# oc75_v5.net
KiCad netlist of a schematic drawn in EAGLE
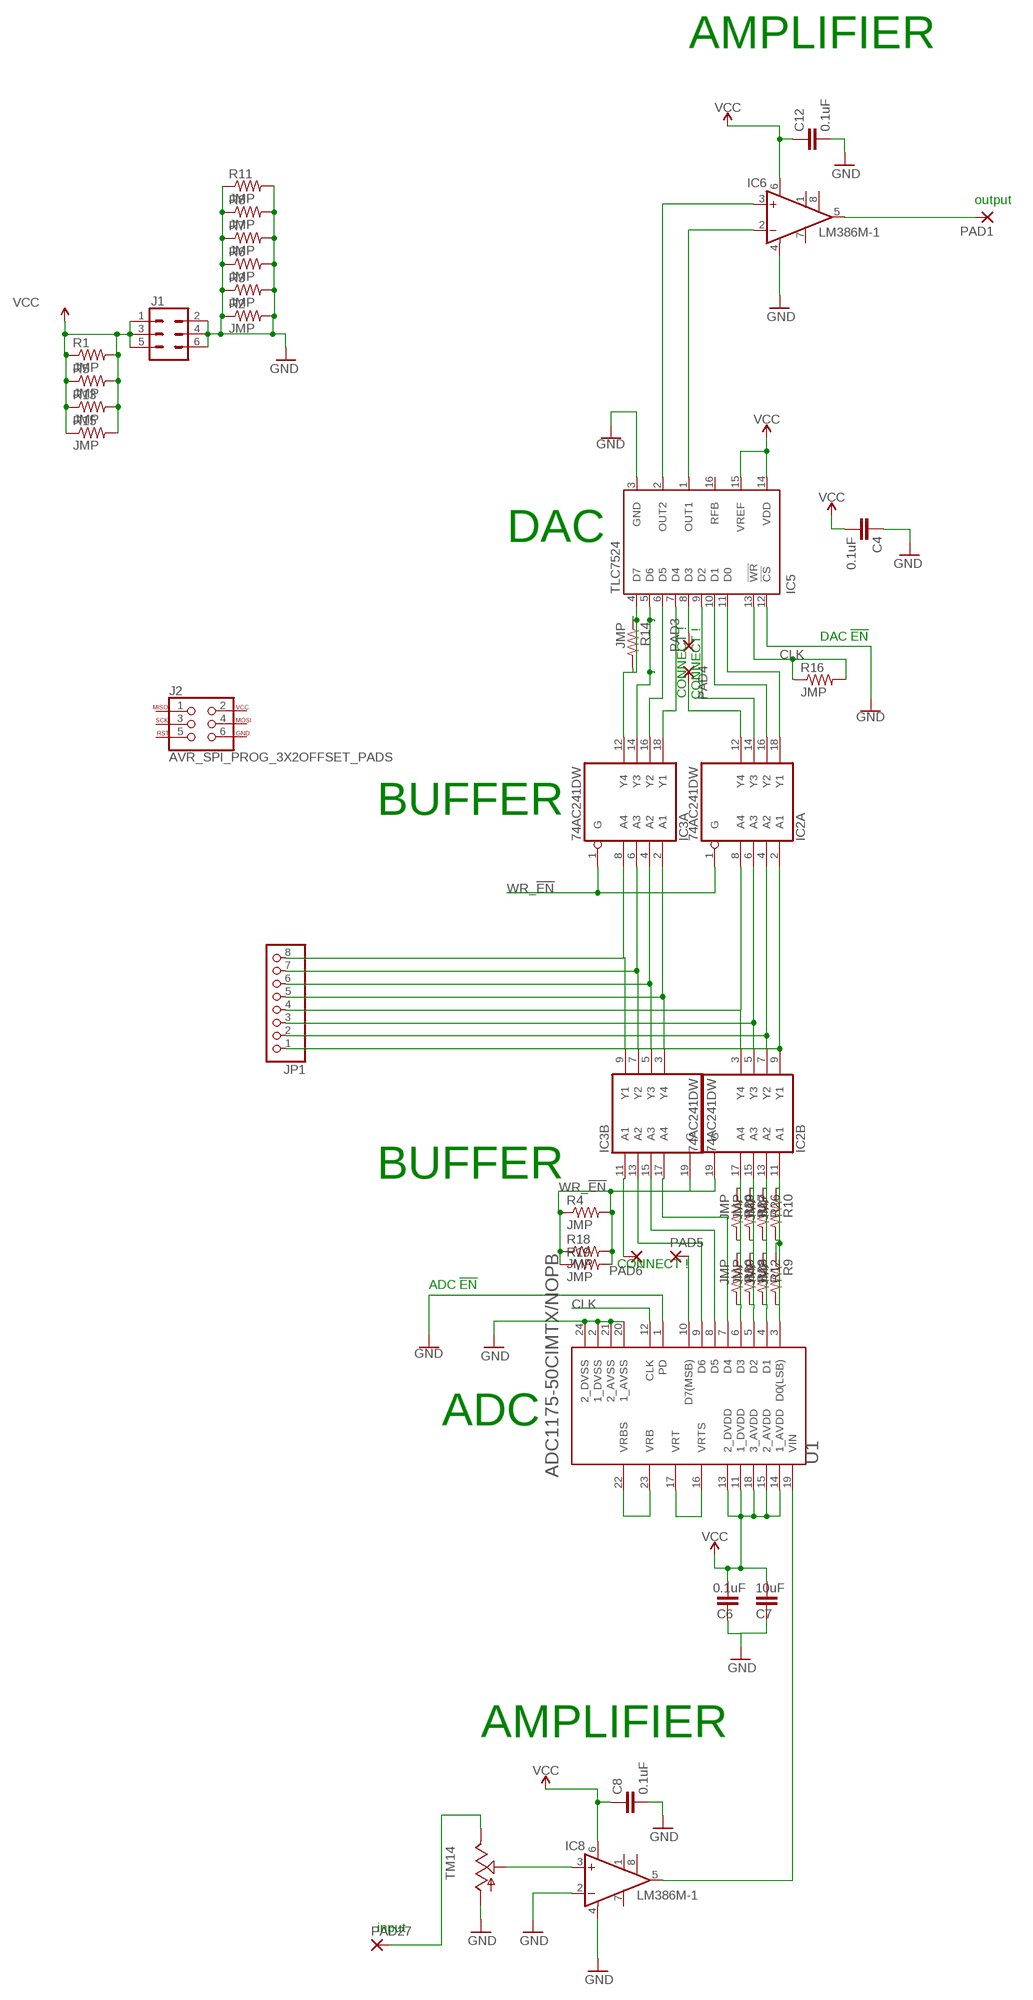
[diagram p0: schematic, sheet 1]

(export (version "E")
  (design (tool "Eeschema 10.0.6"))
  (components
    (comp (ref "C4")
      (value "0.1uF")
      (footprint "eagle-import:1206")
      (libsource (lib "eagle-import") (part "1.0UF-1206-50V-10%"))
    )
    (comp (ref "C6")
      (value "0.1uF")
      (footprint "eagle-import:1206")
      (libsource (lib "eagle-import") (part "1.0UF-1206-50V-10%"))
    )
    (comp (ref "C7")
      (value "10uF")
      (footprint "eagle-import:1206")
      (libsource (lib "eagle-import") (part "1.0UF-1206-50V-10%"))
    )
    (comp (ref "C8")
      (value "0.1uF")
      (footprint "eagle-import:1206")
      (libsource (lib "eagle-import") (part "1.0UF-1206-50V-10%"))
    )
    (comp (ref "C12")
      (value "0.1uF")
      (footprint "eagle-import:1206")
      (libsource (lib "eagle-import") (part "1.0UF-1206-50V-10%"))
    )
    (comp (ref "IC2")
      (value "74AC241DW")
      (footprint "eagle-import:SO20W")
      (libsource (lib "eagle-import") (part "74241DWAC"))
    )
    (comp (ref "IC3")
      (value "74AC241DW")
      (footprint "eagle-import:SO20W")
      (libsource (lib "eagle-import") (part "74241DWAC"))
    )
    (comp (ref "IC5")
      (value "TLC7524")
      (footprint "eagle-import:SO16")
      (libsource (lib "eagle-import") (part "TLC7524"))
    )
    (comp (ref "IC6")
      (value "LM386M-1")
      (footprint "eagle-import:SO08")
      (libsource (lib "eagle-import") (part "LM386?-M1"))
    )
    (comp (ref "IC8")
      (value "LM386M-1")
      (footprint "eagle-import:SO08")
      (libsource (lib "eagle-import") (part "LM386?-M1"))
    )
    (comp (ref "J1")
      (value "CONN_03X2FEMALE_SMD")
      (footprint "eagle-import:2X3_SMD")
      (libsource (lib "eagle-import") (part "CONN_03X2FEMALE_SMD"))
    )
    (comp (ref "J2")
      (value "AVR_SPI_PROG_3X2OFFSET_PADS")
      (footprint "eagle-import:2X3_OFFSET")
      (libsource (lib "eagle-import") (part "AVR_SPI_PROG_3X2OFFSET_PADS"))
    )
    (comp (ref "JP1")
      (value "PINHD-1X8BIG")
      (footprint "eagle-import:1X08-BIG")
      (libsource (lib "eagle-import") (part "PINHD-1X8BIG"))
    )
    (comp (ref "PAD1")
      (value "SMD2")
      (footprint "eagle-import:SMD1,27-2,54")
      (libsource (lib "eagle-import") (part "SMD2"))
    )
    (comp (ref "PAD3")
      (value "SMD2")
      (footprint "eagle-import:SMD1,27-2,54")
      (libsource (lib "eagle-import") (part "SMD2"))
    )
    (comp (ref "PAD4")
      (value "SMD2")
      (footprint "eagle-import:SMD1,27-2,54")
      (libsource (lib "eagle-import") (part "SMD2"))
    )
    (comp (ref "PAD5")
      (value "SMD2")
      (footprint "eagle-import:SMD1,27-2,54")
      (libsource (lib "eagle-import") (part "SMD2"))
    )
    (comp (ref "PAD6")
      (value "SMD2")
      (footprint "eagle-import:SMD1,27-2,54")
      (libsource (lib "eagle-import") (part "SMD2"))
    )
    (comp (ref "PAD27")
      (value "SMD2")
      (footprint "eagle-import:SMD1,27-2,54")
      (libsource (lib "eagle-import") (part "SMD2"))
    )
    (comp (ref "R1")
      (value "JMP")
      (footprint "eagle-import:M1206")
      (libsource (lib "eagle-import") (part "R-US_M1206"))
    )
    (comp (ref "R2")
      (value "JMP")
      (footprint "eagle-import:M1206")
      (libsource (lib "eagle-import") (part "R-US_M1206"))
    )
    (comp (ref "R3")
      (value "JMP")
      (footprint "eagle-import:M1206")
      (libsource (lib "eagle-import") (part "R-US_M1206"))
    )
    (comp (ref "R4")
      (value "JMP")
      (footprint "eagle-import:M1206")
      (libsource (lib "eagle-import") (part "R-US_M1206"))
    )
    (comp (ref "R5")
      (value "JMP")
      (footprint "eagle-import:M1206")
      (libsource (lib "eagle-import") (part "R-US_M1206"))
    )
    (comp (ref "R6")
      (value "JMP")
      (footprint "eagle-import:M1206")
      (libsource (lib "eagle-import") (part "R-US_M1206"))
    )
    (comp (ref "R7")
      (value "JMP")
      (footprint "eagle-import:M1206")
      (libsource (lib "eagle-import") (part "R-US_M1206"))
    )
    (comp (ref "R8")
      (value "JMP")
      (footprint "eagle-import:M1206")
      (libsource (lib "eagle-import") (part "R-US_M1206"))
    )
    (comp (ref "R9")
      (value "JMP")
      (footprint "eagle-import:M1206")
      (libsource (lib "eagle-import") (part "R-US_M1206"))
    )
    (comp (ref "R10")
      (value "JMP")
      (footprint "eagle-import:M1206")
      (libsource (lib "eagle-import") (part "R-US_M1206"))
    )
    (comp (ref "R11")
      (value "JMP")
      (footprint "eagle-import:M1206")
      (libsource (lib "eagle-import") (part "R-US_M1206"))
    )
    (comp (ref "R12")
      (value "JMP")
      (footprint "eagle-import:M1206")
      (libsource (lib "eagle-import") (part "R-US_M1206"))
    )
    (comp (ref "R13")
      (value "JMP")
      (footprint "eagle-import:M1206")
      (libsource (lib "eagle-import") (part "R-US_M1206"))
    )
    (comp (ref "R14")
      (value "JMP")
      (footprint "eagle-import:M1206")
      (libsource (lib "eagle-import") (part "R-US_M1206"))
    )
    (comp (ref "R15")
      (value "JMP")
      (footprint "eagle-import:M1206")
      (libsource (lib "eagle-import") (part "R-US_M1206"))
    )
    (comp (ref "R16")
      (value "JMP")
      (footprint "eagle-import:M1206")
      (libsource (lib "eagle-import") (part "R-US_M1206"))
    )
    (comp (ref "R18")
      (value "JMP")
      (footprint "eagle-import:M1206")
      (libsource (lib "eagle-import") (part "R-US_M1206"))
    )
    (comp (ref "R19")
      (value "JMP")
      (footprint "eagle-import:M1206")
      (libsource (lib "eagle-import") (part "R-US_M1206"))
    )
    (comp (ref "R26")
      (value "JMP")
      (footprint "eagle-import:M1206")
      (libsource (lib "eagle-import") (part "R-US_M1206"))
    )
    (comp (ref "R27")
      (value "JMP")
      (footprint "eagle-import:M1206")
      (libsource (lib "eagle-import") (part "R-US_M1206"))
    )
    (comp (ref "R28")
      (value "JMP")
      (footprint "eagle-import:M1206")
      (libsource (lib "eagle-import") (part "R-US_M1206"))
    )
    (comp (ref "R29")
      (value "JMP")
      (footprint "eagle-import:M1206")
      (libsource (lib "eagle-import") (part "R-US_M1206"))
    )
    (comp (ref "R30")
      (value "JMP")
      (footprint "eagle-import:M1206")
      (libsource (lib "eagle-import") (part "R-US_M1206"))
    )
    (comp (ref "TM14")
      (value "TRIM")
      (footprint "eagle-import:6MM")
      (libsource (lib "eagle-import") (part "TRIM"))
    )
    (comp (ref "U1")
      (value "TEXAS_INSTRUMENTS_ADC1175-50CIMTX-NOPBTEXAS_INSTRUMENTS_ADC1175-50CIMTX-NOPB_0_0")
      (footprint "eagle-import:TEXAS_INSTRUMENTS_ADC1175-50CIMTX-NOPB_0")
      (fields
        (field (name "DIGIKEY_PART_NUMBER") "296-36905-1-ND")
        (field (name "MF") "Texas Instruments")
        (field (name "MOUSER_PART_NUMBER") "926-AD117550CIMTXNPB")
      )
      (libsource (lib "eagle-import") (part "TEXAS_INSTRUMENTS_ADC1175-50CIMTX-NOPBTEXAS_INSTRUMENTS_ADC1175-50CIMTX-NOPB_0_0"))
    )
  )
  (nets
    (net (code "1") (name "/CLK") (class "Default")
      (node (ref "IC5") (pin "13") (pinfunction "~{WR}_13") (pintype "input"))
      (node (ref "R16") (pin "1") (pinfunction "1_1") (pintype "passive"))
      (node (ref "R16") (pin "2") (pinfunction "2_2") (pintype "passive"))
      (node (ref "U1") (pin "12") (pinfunction "CLK_12") (pintype "bidirectional"))
    )
    (net (code "2") (name "/WR_~{EN}") (class "Default")
      (node (ref "IC2") (pin "1") (pinfunction "G_1") (pintype "input"))
      (node (ref "IC2") (pin "19") (pinfunction "G_19") (pintype "input"))
      (node (ref "IC3") (pin "1") (pinfunction "G_1") (pintype "input"))
      (node (ref "IC3") (pin "19") (pinfunction "G_19") (pintype "input"))
      (node (ref "R18") (pin "1") (pinfunction "1_1") (pintype "passive"))
      (node (ref "R18") (pin "2") (pinfunction "2_2") (pintype "passive"))
      (node (ref "R19") (pin "1") (pinfunction "1_1") (pintype "passive"))
      (node (ref "R19") (pin "2") (pinfunction "2_2") (pintype "passive"))
      (node (ref "R4") (pin "1") (pinfunction "1_1") (pintype "passive"))
      (node (ref "R4") (pin "2") (pinfunction "2_2") (pintype "passive"))
    )
    (net (code "3") (name "GND") (class "Default")
      (node (ref "C12") (pin "2") (pinfunction "2_2") (pintype "passive"))
      (node (ref "C4") (pin "1") (pinfunction "1_1") (pintype "passive"))
      (node (ref "C6") (pin "1") (pinfunction "1_1") (pintype "passive"))
      (node (ref "C7") (pin "1") (pinfunction "1_1") (pintype "passive"))
      (node (ref "C8") (pin "2") (pinfunction "2_2") (pintype "passive"))
      (node (ref "IC5") (pin "12") (pinfunction "~{CS}_12") (pintype "input"))
      (node (ref "IC5") (pin "3") (pinfunction "GND_3") (pintype "power_in"))
      (node (ref "IC6") (pin "4") (pinfunction "GND_4") (pintype "power_in"))
      (node (ref "IC8") (pin "2") (pinfunction "-IN_2") (pintype "input"))
      (node (ref "IC8") (pin "4") (pinfunction "GND_4") (pintype "power_in"))
      (node (ref "J1") (pin "2") (pinfunction "2_2") (pintype "bidirectional"))
      (node (ref "J1") (pin "4") (pinfunction "4_4") (pintype "bidirectional"))
      (node (ref "J1") (pin "6") (pinfunction "6_6") (pintype "bidirectional"))
      (node (ref "R11") (pin "1") (pinfunction "1_1") (pintype "passive"))
      (node (ref "R11") (pin "2") (pinfunction "2_2") (pintype "passive"))
      (node (ref "R2") (pin "1") (pinfunction "1_1") (pintype "passive"))
      (node (ref "R2") (pin "2") (pinfunction "2_2") (pintype "passive"))
      (node (ref "R3") (pin "1") (pinfunction "1_1") (pintype "passive"))
      (node (ref "R3") (pin "2") (pinfunction "2_2") (pintype "passive"))
      (node (ref "R6") (pin "1") (pinfunction "1_1") (pintype "passive"))
      (node (ref "R6") (pin "2") (pinfunction "2_2") (pintype "passive"))
      (node (ref "R7") (pin "1") (pinfunction "1_1") (pintype "passive"))
      (node (ref "R7") (pin "2") (pinfunction "2_2") (pintype "passive"))
      (node (ref "R8") (pin "1") (pinfunction "1_1") (pintype "passive"))
      (node (ref "R8") (pin "2") (pinfunction "2_2") (pintype "passive"))
      (node (ref "TM14") (pin "A") (pinfunction "A_A") (pintype "passive"))
      (node (ref "U1") (pin "1") (pinfunction "PD_1") (pintype "bidirectional"))
      (node (ref "U1") (pin "2") (pinfunction "1_DVSS_2") (pintype "bidirectional"))
      (node (ref "U1") (pin "20") (pinfunction "1_AVSS_20") (pintype "bidirectional"))
      (node (ref "U1") (pin "21") (pinfunction "2_AVSS_21") (pintype "bidirectional"))
      (node (ref "U1") (pin "24") (pinfunction "2_DVSS_24") (pintype "bidirectional"))
    )
    (net (code "4") (name "Net-(IC2A-A1)") (class "Default")
      (node (ref "IC2") (pin "2") (pinfunction "A1_2") (pintype "input"))
      (node (ref "IC2") (pin "9") (pinfunction "Y1_9") (pintype "tri_state"))
      (node (ref "JP1") (pin "1") (pinfunction "1_1") (pintype "passive"))
    )
    (net (code "5") (name "Net-(IC2A-A2)") (class "Default")
      (node (ref "IC2") (pin "4") (pinfunction "A2_4") (pintype "input"))
      (node (ref "IC2") (pin "7") (pinfunction "Y2_7") (pintype "tri_state"))
      (node (ref "JP1") (pin "2") (pinfunction "2_2") (pintype "passive"))
    )
    (net (code "6") (name "Net-(IC2A-A3)") (class "Default")
      (node (ref "IC2") (pin "5") (pinfunction "Y3_5") (pintype "tri_state"))
      (node (ref "IC2") (pin "6") (pinfunction "A3_6") (pintype "input"))
      (node (ref "JP1") (pin "3") (pinfunction "3_3") (pintype "passive"))
    )
    (net (code "7") (name "Net-(IC2A-A4)") (class "Default")
      (node (ref "IC2") (pin "3") (pinfunction "Y4_3") (pintype "tri_state"))
      (node (ref "IC2") (pin "8") (pinfunction "A4_8") (pintype "input"))
      (node (ref "JP1") (pin "4") (pinfunction "4_4") (pintype "passive"))
    )
    (net (code "8") (name "Net-(IC2A-Y1)") (class "Default")
      (node (ref "IC2") (pin "18") (pinfunction "Y1_18") (pintype "tri_state"))
      (node (ref "IC5") (pin "11") (pinfunction "D0_11") (pintype "input"))
    )
    (net (code "9") (name "Net-(IC2A-Y2)") (class "Default")
      (node (ref "IC2") (pin "16") (pinfunction "Y2_16") (pintype "tri_state"))
      (node (ref "IC5") (pin "10") (pinfunction "D1_10") (pintype "input"))
    )
    (net (code "10") (name "Net-(IC2A-Y3)") (class "Default")
      (node (ref "IC2") (pin "14") (pinfunction "Y3_14") (pintype "tri_state"))
      (node (ref "IC5") (pin "9") (pinfunction "D2_9") (pintype "input"))
    )
    (net (code "11") (name "Net-(IC2A-Y4)") (class "Default")
      (node (ref "IC2") (pin "12") (pinfunction "Y4_12") (pintype "tri_state"))
      (node (ref "PAD4") (pin "1") (pinfunction "P_1") (pintype "passive"))
    )
    (net (code "12") (name "Net-(IC2B-A1)") (class "Default")
      (node (ref "IC2") (pin "11") (pinfunction "A1_11") (pintype "input"))
      (node (ref "R10") (pin "1") (pinfunction "1_1") (pintype "passive"))
      (node (ref "R10") (pin "2") (pinfunction "2_2") (pintype "passive"))
      (node (ref "R9") (pin "1") (pinfunction "1_1") (pintype "passive"))
      (node (ref "R9") (pin "2") (pinfunction "2_2") (pintype "passive"))
      (node (ref "U1") (pin "3") (pinfunction "D0(LSB)_3") (pintype "bidirectional"))
    )
    (net (code "13") (name "Net-(IC2B-A2)") (class "Default")
      (node (ref "IC2") (pin "13") (pinfunction "A2_13") (pintype "input"))
      (node (ref "R12") (pin "1") (pinfunction "1_1") (pintype "passive"))
      (node (ref "R12") (pin "2") (pinfunction "2_2") (pintype "passive"))
      (node (ref "R26") (pin "1") (pinfunction "1_1") (pintype "passive"))
      (node (ref "R26") (pin "2") (pinfunction "2_2") (pintype "passive"))
      (node (ref "U1") (pin "4") (pinfunction "D1_4") (pintype "bidirectional"))
    )
    (net (code "14") (name "Net-(IC2B-A3)") (class "Default")
      (node (ref "IC2") (pin "15") (pinfunction "A3_15") (pintype "input"))
      (node (ref "R27") (pin "1") (pinfunction "1_1") (pintype "passive"))
      (node (ref "R27") (pin "2") (pinfunction "2_2") (pintype "passive"))
      (node (ref "R28") (pin "1") (pinfunction "1_1") (pintype "passive"))
      (node (ref "R28") (pin "2") (pinfunction "2_2") (pintype "passive"))
      (node (ref "U1") (pin "5") (pinfunction "D2_5") (pintype "bidirectional"))
    )
    (net (code "15") (name "Net-(IC2B-A4)") (class "Default")
      (node (ref "IC2") (pin "17") (pinfunction "A4_17") (pintype "input"))
      (node (ref "R29") (pin "1") (pinfunction "1_1") (pintype "passive"))
      (node (ref "R29") (pin "2") (pinfunction "2_2") (pintype "passive"))
      (node (ref "R30") (pin "1") (pinfunction "1_1") (pintype "passive"))
      (node (ref "R30") (pin "2") (pinfunction "2_2") (pintype "passive"))
      (node (ref "U1") (pin "6") (pinfunction "D3_6") (pintype "bidirectional"))
    )
    (net (code "16") (name "Net-(IC3A-A1)") (class "Default")
      (node (ref "IC3") (pin "2") (pinfunction "A1_2") (pintype "input"))
      (node (ref "IC3") (pin "3") (pinfunction "Y4_3") (pintype "tri_state"))
      (node (ref "JP1") (pin "5") (pinfunction "5_5") (pintype "passive"))
    )
    (net (code "17") (name "Net-(IC3A-A2)") (class "Default")
      (node (ref "IC3") (pin "4") (pinfunction "A2_4") (pintype "input"))
      (node (ref "IC3") (pin "5") (pinfunction "Y3_5") (pintype "tri_state"))
      (node (ref "JP1") (pin "6") (pinfunction "6_6") (pintype "passive"))
    )
    (net (code "18") (name "Net-(IC3A-A3)") (class "Default")
      (node (ref "IC3") (pin "6") (pinfunction "A3_6") (pintype "input"))
      (node (ref "IC3") (pin "7") (pinfunction "Y2_7") (pintype "tri_state"))
      (node (ref "JP1") (pin "7") (pinfunction "7_7") (pintype "passive"))
    )
    (net (code "19") (name "Net-(IC3A-A4)") (class "Default")
      (node (ref "IC3") (pin "8") (pinfunction "A4_8") (pintype "input"))
      (node (ref "IC3") (pin "9") (pinfunction "Y1_9") (pintype "tri_state"))
      (node (ref "JP1") (pin "8") (pinfunction "8_8") (pintype "passive"))
    )
    (net (code "20") (name "Net-(IC3A-Y1)") (class "Default")
      (node (ref "IC3") (pin "18") (pinfunction "Y1_18") (pintype "tri_state"))
      (node (ref "IC5") (pin "7") (pinfunction "D4_7") (pintype "input"))
    )
    (net (code "21") (name "Net-(IC3A-Y2)") (class "Default")
      (node (ref "IC3") (pin "16") (pinfunction "Y2_16") (pintype "tri_state"))
      (node (ref "IC5") (pin "6") (pinfunction "D5_6") (pintype "input"))
    )
    (net (code "22") (name "Net-(IC3A-Y3)") (class "Default")
      (node (ref "IC3") (pin "14") (pinfunction "Y3_14") (pintype "tri_state"))
      (node (ref "IC5") (pin "5") (pinfunction "D6_5") (pintype "input"))
    )
    (net (code "23") (name "Net-(IC3A-Y4)") (class "Default")
      (node (ref "IC3") (pin "12") (pinfunction "Y4_12") (pintype "tri_state"))
      (node (ref "IC5") (pin "4") (pinfunction "D7_4") (pintype "input"))
      (node (ref "R14") (pin "1") (pinfunction "1_1") (pintype "passive"))
      (node (ref "R14") (pin "2") (pinfunction "2_2") (pintype "passive"))
    )
    (net (code "24") (name "Net-(IC3B-A1)") (class "Default")
      (node (ref "IC3") (pin "11") (pinfunction "A1_11") (pintype "input"))
      (node (ref "PAD6") (pin "1") (pinfunction "P_1") (pintype "passive"))
    )
    (net (code "25") (name "Net-(IC3B-A2)") (class "Default")
      (node (ref "IC3") (pin "13") (pinfunction "A2_13") (pintype "input"))
      (node (ref "U1") (pin "9") (pinfunction "D6_9") (pintype "bidirectional"))
    )
    (net (code "26") (name "Net-(IC3B-A3)") (class "Default")
      (node (ref "IC3") (pin "15") (pinfunction "A3_15") (pintype "input"))
      (node (ref "U1") (pin "8") (pinfunction "D5_8") (pintype "bidirectional"))
    )
    (net (code "27") (name "Net-(IC3B-A4)") (class "Default")
      (node (ref "IC3") (pin "17") (pinfunction "A4_17") (pintype "input"))
      (node (ref "U1") (pin "7") (pinfunction "D4_7") (pintype "bidirectional"))
    )
    (net (code "28") (name "Net-(IC5-D3)") (class "Default")
      (node (ref "IC5") (pin "8") (pinfunction "D3_8") (pintype "input"))
      (node (ref "PAD3") (pin "1") (pinfunction "P_1") (pintype "passive"))
    )
    (net (code "29") (name "Net-(IC5-OUT1)") (class "Default")
      (node (ref "IC5") (pin "1") (pinfunction "OUT1_1") (pintype "passive"))
      (node (ref "IC6") (pin "2") (pinfunction "-IN_2") (pintype "input"))
    )
    (net (code "30") (name "Net-(IC5-OUT2)") (class "Default")
      (node (ref "IC5") (pin "2") (pinfunction "OUT2_2") (pintype "passive"))
      (node (ref "IC6") (pin "3") (pinfunction "+IN_3") (pintype "input"))
    )
    (net (code "31") (name "Net-(IC6-OUT)") (class "Default")
      (node (ref "IC6") (pin "5") (pinfunction "OUT_5") (pintype "output"))
      (node (ref "PAD1") (pin "1") (pinfunction "P_1") (pintype "passive"))
    )
    (net (code "32") (name "Net-(IC8-+IN)") (class "Default")
      (node (ref "IC8") (pin "3") (pinfunction "+IN_3") (pintype "input"))
      (node (ref "TM14") (pin "S") (pinfunction "S_S") (pintype "passive"))
    )
    (net (code "33") (name "Net-(IC8-OUT)") (class "Default")
      (node (ref "IC8") (pin "5") (pinfunction "OUT_5") (pintype "output"))
      (node (ref "U1") (pin "19") (pinfunction "VIN_19") (pintype "bidirectional"))
    )
    (net (code "34") (name "Net-(PAD5-P)") (class "Default")
      (node (ref "PAD5") (pin "1") (pinfunction "P_1") (pintype "passive"))
      (node (ref "U1") (pin "10") (pinfunction "D7(MSB)_10") (pintype "bidirectional"))
    )
    (net (code "35") (name "Net-(PAD27-P)") (class "Default")
      (node (ref "PAD27") (pin "1") (pinfunction "P_1") (pintype "passive"))
      (node (ref "TM14") (pin "E") (pinfunction "E_E") (pintype "passive"))
    )
    (net (code "36") (name "Net-(U1-VRB)") (class "Default")
      (node (ref "U1") (pin "22") (pinfunction "VRBS_22") (pintype "bidirectional"))
      (node (ref "U1") (pin "23") (pinfunction "VRB_23") (pintype "bidirectional"))
    )
    (net (code "37") (name "Net-(U1-VRT)") (class "Default")
      (node (ref "U1") (pin "16") (pinfunction "VRTS_16") (pintype "bidirectional"))
      (node (ref "U1") (pin "17") (pinfunction "VRT_17") (pintype "bidirectional"))
    )
    (net (code "38") (name "VCC") (class "Default")
      (node (ref "C12") (pin "1") (pinfunction "1_1") (pintype "passive"))
      (node (ref "C4") (pin "2") (pinfunction "2_2") (pintype "passive"))
      (node (ref "C6") (pin "2") (pinfunction "2_2") (pintype "passive"))
      (node (ref "C7") (pin "2") (pinfunction "2_2") (pintype "passive"))
      (node (ref "C8") (pin "1") (pinfunction "1_1") (pintype "passive"))
      (node (ref "IC5") (pin "14") (pinfunction "VDD_14") (pintype "power_in"))
      (node (ref "IC5") (pin "15") (pinfunction "VREF_15") (pintype "input"))
      (node (ref "IC6") (pin "6") (pinfunction "VS_6") (pintype "power_in"))
      (node (ref "IC8") (pin "6") (pinfunction "VS_6") (pintype "power_in"))
      (node (ref "J1") (pin "1") (pinfunction "1_1") (pintype "bidirectional"))
      (node (ref "J1") (pin "3") (pinfunction "3_3") (pintype "bidirectional"))
      (node (ref "J1") (pin "5") (pinfunction "5_5") (pintype "bidirectional"))
      (node (ref "R1") (pin "1") (pinfunction "1_1") (pintype "passive"))
      (node (ref "R1") (pin "2") (pinfunction "2_2") (pintype "passive"))
      (node (ref "R13") (pin "1") (pinfunction "1_1") (pintype "passive"))
      (node (ref "R13") (pin "2") (pinfunction "2_2") (pintype "passive"))
      (node (ref "R15") (pin "1") (pinfunction "1_1") (pintype "passive"))
      (node (ref "R15") (pin "2") (pinfunction "2_2") (pintype "passive"))
      (node (ref "R5") (pin "1") (pinfunction "1_1") (pintype "passive"))
      (node (ref "R5") (pin "2") (pinfunction "2_2") (pintype "passive"))
      (node (ref "U1") (pin "11") (pinfunction "1_DVDD_11") (pintype "bidirectional"))
      (node (ref "U1") (pin "13") (pinfunction "2_DVDD_13") (pintype "bidirectional"))
      (node (ref "U1") (pin "14") (pinfunction "1_AVDD_14") (pintype "bidirectional"))
      (node (ref "U1") (pin "15") (pinfunction "2_AVDD_15") (pintype "bidirectional"))
      (node (ref "U1") (pin "18") (pinfunction "3_AVDD_18") (pintype "bidirectional"))
    )
    (net (code "39") (name "unconnected-(IC5-RFB-Pad16)") (class "Default")
      (node (ref "IC5") (pin "16") (pinfunction "RFB_16") (pintype "passive"))
    )
    (net (code "40") (name "unconnected-(IC6-BYPASS-Pad7)") (class "Default")
      (node (ref "IC6") (pin "7") (pinfunction "BYPASS_7") (pintype "passive"))
    )
    (net (code "41") (name "unconnected-(IC6-GAIN-Pad1)") (class "Default")
      (node (ref "IC6") (pin "1") (pinfunction "GAIN_1") (pintype "passive"))
    )
    (net (code "42") (name "unconnected-(IC6-GAIN-Pad8)") (class "Default")
      (node (ref "IC6") (pin "8") (pinfunction "GAIN_8") (pintype "passive"))
    )
    (net (code "43") (name "unconnected-(IC8-BYPASS-Pad7)") (class "Default")
      (node (ref "IC8") (pin "7") (pinfunction "BYPASS_7") (pintype "passive"))
    )
    (net (code "44") (name "unconnected-(IC8-GAIN-Pad1)") (class "Default")
      (node (ref "IC8") (pin "1") (pinfunction "GAIN_1") (pintype "passive"))
    )
    (net (code "45") (name "unconnected-(IC8-GAIN-Pad8)") (class "Default")
      (node (ref "IC8") (pin "8") (pinfunction "GAIN_8") (pintype "passive"))
    )
    (net (code "46") (name "unconnected-(J2-Pad1)") (class "Default")
      (node (ref "J2") (pin "1") (pinfunction "1_1") (pintype "passive"))
    )
    (net (code "47") (name "unconnected-(J2-Pad2)") (class "Default")
      (node (ref "J2") (pin "2") (pinfunction "2_2") (pintype "passive"))
    )
    (net (code "48") (name "unconnected-(J2-Pad3)") (class "Default")
      (node (ref "J2") (pin "3") (pinfunction "3_3") (pintype "passive"))
    )
    (net (code "49") (name "unconnected-(J2-Pad4)") (class "Default")
      (node (ref "J2") (pin "4") (pinfunction "4_4") (pintype "passive"))
    )
    (net (code "50") (name "unconnected-(J2-Pad5)") (class "Default")
      (node (ref "J2") (pin "5") (pinfunction "5_5") (pintype "passive"))
    )
    (net (code "51") (name "unconnected-(J2-Pad6)") (class "Default")
      (node (ref "J2") (pin "6") (pinfunction "6_6") (pintype "passive"))
    )
  )
)
